# AUDIO.net
KiCad netlist of a schematic drawn in Altium Designer
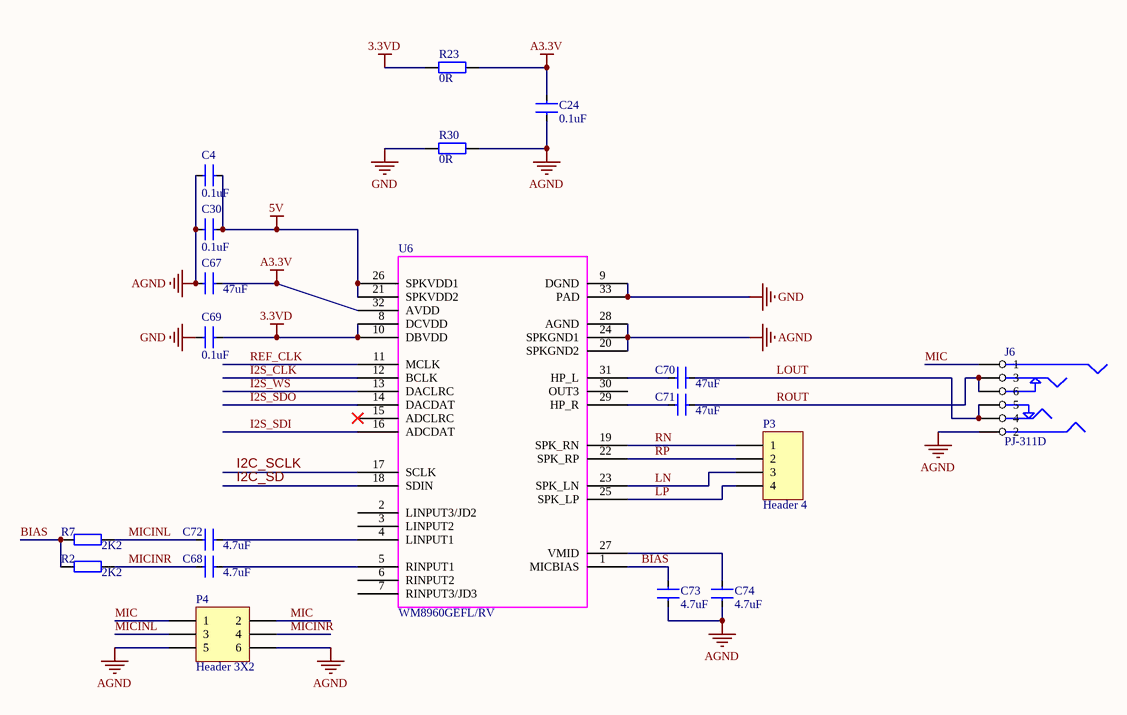
[diagram p0: AUDIO.SchDoc]

(export (version "E")
  (design (tool "Eeschema 10.0.6"))
  (components
    (comp (ref "C4")
      (value "0.1uF")
      (footprint "C0402")
      (description "普通小电容")
      (libsource (lib "LIB_MANGO") (part "CAP"))
    )
    (comp (ref "C24")
      (value "0.1uF")
      (footprint "C0402")
      (description "普通小电容")
      (libsource (lib "LIB_MANGO") (part "CAP"))
    )
    (comp (ref "C30")
      (value "0.1uF")
      (footprint "C0402")
      (description "普通小电容")
      (libsource (lib "LIB_MANGO") (part "CAP"))
    )
    (comp (ref "C67")
      (value "47uF")
      (footprint "0805C")
      (description "普通小电容")
      (libsource (lib "LIB_MANGO") (part "CAP"))
    )
    (comp (ref "C68")
      (value "4.7uF")
      (footprint "C0402")
      (description "普通小电容")
      (libsource (lib "LIB_MANGO") (part "CAP"))
    )
    (comp (ref "C69")
      (value "0.1uF")
      (footprint "C0402")
      (description "普通小电容")
      (libsource (lib "LIB_MANGO") (part "CAP"))
    )
    (comp (ref "C70")
      (value "47uF")
      (footprint "0805C")
      (description "普通小电容")
      (libsource (lib "LIB_MANGO") (part "CAP"))
    )
    (comp (ref "C71")
      (value "47uF")
      (footprint "0805C")
      (description "普通小电容")
      (libsource (lib "LIB_MANGO") (part "CAP"))
    )
    (comp (ref "C72")
      (value "4.7uF")
      (footprint "C0402")
      (description "普通小电容")
      (libsource (lib "LIB_MANGO") (part "CAP"))
    )
    (comp (ref "C73")
      (value "4.7uF")
      (footprint "C0402")
      (description "普通小电容")
      (libsource (lib "LIB_MANGO") (part "CAP"))
    )
    (comp (ref "C74")
      (value "4.7uF")
      (footprint "C0402")
      (description "普通小电容")
      (libsource (lib "LIB_MANGO") (part "CAP"))
    )
    (comp (ref "J6") (value "PJ-311D") (footprint "PJ311D") (libsource (lib "LIB_MANGO") (part "PJ-311D")))
    (comp (ref "P3")
      (value "Header 4")
      (footprint "HDR1X4 -2.0")
      (description "Header, 4-Pin")
      (fields (field (name "PUBLISHER") "Altium Limited"))
      (libsource (lib "LIB_MANGO") (part "Header 4"))
    )
    (comp (ref "P4")
      (value "Header 3X2")
      (footprint "HDR2X3 - 2.0")
      (description "Header, 3-Pin, Dual row")
      (fields (field (name "PUBLISHER") "Altium Limited"))
      (libsource (lib "LIB_MANGO") (part "Header 3X2"))
    )
    (comp (ref "R2")
      (value "2K2")
      (footprint "R0402")
      (description "普通电阻")
      (libsource (lib "LIB_MANGO") (part "RES"))
    )
    (comp (ref "R7")
      (value "2K2")
      (footprint "R0402")
      (description "普通电阻")
      (libsource (lib "LIB_MANGO") (part "RES"))
    )
    (comp (ref "R23")
      (value "0R")
      (footprint "R0402")
      (description "普通电阻")
      (libsource (lib "LIB_MANGO") (part "RES"))
    )
    (comp (ref "R30")
      (value "0R")
      (footprint "R0402")
      (description "普通电阻")
      (libsource (lib "LIB_MANGO") (part "RES"))
    )
    (comp (ref "U6")
      (value "WM8960GEFL/RV")
      (footprint "QFN50P500X500X100-33N")
      (libsource (lib "ALL") (part "WM8960GEFL/RV"))
    )
  )
  (nets
    (net (code "1") (name "/BIAS") (class "Default")
      (node (ref "C73") (pin "2") (pinfunction "2_2") (pintype "passive"))
      (node (ref "R2") (pin "1") (pinfunction "1_1") (pintype "passive"))
      (node (ref "R7") (pin "1") (pinfunction "1_1") (pintype "passive"))
      (node (ref "U6") (pin "1") (pinfunction "MICBIAS_1") (pintype "passive"))
    )
    (net (code "2") (name "/I2C_SCLK") (class "Default")
      (node (ref "U6") (pin "17") (pinfunction "SCLK_17") (pintype "passive"))
    )
    (net (code "3") (name "/I2C_SD") (class "Default")
      (node (ref "U6") (pin "18") (pinfunction "SDIN_18") (pintype "passive"))
    )
    (net (code "4") (name "/I2S_CLK") (class "Default")
      (node (ref "U6") (pin "12") (pinfunction "BCLK_12") (pintype "passive"))
    )
    (net (code "5") (name "/I2S_SDI") (class "Default")
      (node (ref "U6") (pin "16") (pinfunction "ADCDAT_16") (pintype "passive"))
    )
    (net (code "6") (name "/I2S_SDO") (class "Default")
      (node (ref "U6") (pin "14") (pinfunction "DACDAT_14") (pintype "passive"))
    )
    (net (code "7") (name "/I2S_WS") (class "Default")
      (node (ref "U6") (pin "13") (pinfunction "DACLRC_13") (pintype "passive"))
    )
    (net (code "8") (name "/LN") (class "Default")
      (node (ref "P3") (pin "3") (pinfunction "3_3") (pintype "passive"))
      (node (ref "U6") (pin "23") (pinfunction "SPK_LN_23") (pintype "passive"))
    )
    (net (code "9") (name "/LOUT") (class "Default")
      (node (ref "C70") (pin "1") (pinfunction "1_1") (pintype "passive"))
      (node (ref "J6") (pin "4") (pinfunction "4_4") (pintype "passive"))
      (node (ref "J6") (pin "5") (pinfunction "5_5") (pintype "passive"))
    )
    (net (code "10") (name "/LP") (class "Default")
      (node (ref "P3") (pin "4") (pinfunction "4_4") (pintype "passive"))
      (node (ref "U6") (pin "25") (pinfunction "SPK_LP_25") (pintype "passive"))
    )
    (net (code "11") (name "/MIC") (class "Default")
      (node (ref "J6") (pin "1") (pinfunction "1_1") (pintype "passive"))
      (node (ref "P4") (pin "1") (pinfunction "1_1") (pintype "passive"))
      (node (ref "P4") (pin "2") (pinfunction "2_2") (pintype "passive"))
    )
    (net (code "12") (name "/MICINL") (class "Default")
      (node (ref "C72") (pin "2") (pinfunction "2_2") (pintype "passive"))
      (node (ref "P4") (pin "3") (pinfunction "3_3") (pintype "passive"))
      (node (ref "R7") (pin "2") (pinfunction "2_2") (pintype "passive"))
    )
    (net (code "13") (name "/MICINR") (class "Default")
      (node (ref "C68") (pin "2") (pinfunction "2_2") (pintype "passive"))
      (node (ref "P4") (pin "4") (pinfunction "4_4") (pintype "passive"))
      (node (ref "R2") (pin "2") (pinfunction "2_2") (pintype "passive"))
    )
    (net (code "14") (name "/REF_CLK") (class "Default")
      (node (ref "U6") (pin "11") (pinfunction "MCLK_11") (pintype "passive"))
    )
    (net (code "15") (name "/RN") (class "Default")
      (node (ref "P3") (pin "1") (pinfunction "1_1") (pintype "passive"))
      (node (ref "U6") (pin "19") (pinfunction "SPK_RN_19") (pintype "passive"))
    )
    (net (code "16") (name "/ROUT") (class "Default")
      (node (ref "C71") (pin "1") (pinfunction "1_1") (pintype "passive"))
      (node (ref "J6") (pin "3") (pinfunction "3_3") (pintype "passive"))
      (node (ref "J6") (pin "6") (pinfunction "6_6") (pintype "passive"))
    )
    (net (code "17") (name "/RP") (class "Default")
      (node (ref "P3") (pin "2") (pinfunction "2_2") (pintype "passive"))
      (node (ref "U6") (pin "22") (pinfunction "SPK_RP_22") (pintype "passive"))
    )
    (net (code "18") (name "3.3VD") (class "Default")
      (node (ref "C69") (pin "2") (pinfunction "2_2") (pintype "passive"))
      (node (ref "R23") (pin "1") (pinfunction "1_1") (pintype "passive"))
      (node (ref "U6") (pin "10") (pinfunction "DBVDD_10") (pintype "passive"))
      (node (ref "U6") (pin "8") (pinfunction "DCVDD_8") (pintype "passive"))
    )
    (net (code "19") (name "5V") (class "Default")
      (node (ref "C30") (pin "1") (pinfunction "1_1") (pintype "passive"))
      (node (ref "C4") (pin "1") (pinfunction "1_1") (pintype "passive"))
      (node (ref "U6") (pin "21") (pinfunction "SPKVDD2_21") (pintype "passive"))
      (node (ref "U6") (pin "26") (pinfunction "SPKVDD1_26") (pintype "passive"))
    )
    (net (code "20") (name "A3.3V") (class "Default")
      (node (ref "C24") (pin "2") (pinfunction "2_2") (pintype "passive"))
      (node (ref "C67") (pin "2") (pinfunction "2_2") (pintype "passive"))
      (node (ref "R23") (pin "2") (pinfunction "2_2") (pintype "passive"))
      (node (ref "U6") (pin "32") (pinfunction "AVDD_32") (pintype "passive"))
    )
    (net (code "21") (name "AGND") (class "Default")
      (node (ref "C24") (pin "1") (pinfunction "1_1") (pintype "passive"))
      (node (ref "C30") (pin "2") (pinfunction "2_2") (pintype "passive"))
      (node (ref "C4") (pin "2") (pinfunction "2_2") (pintype "passive"))
      (node (ref "C67") (pin "1") (pinfunction "1_1") (pintype "passive"))
      (node (ref "C73") (pin "1") (pinfunction "1_1") (pintype "passive"))
      (node (ref "C74") (pin "1") (pinfunction "1_1") (pintype "passive"))
      (node (ref "J6") (pin "2") (pinfunction "2_2") (pintype "passive"))
      (node (ref "P4") (pin "5") (pinfunction "5_5") (pintype "passive"))
      (node (ref "P4") (pin "6") (pinfunction "6_6") (pintype "passive"))
      (node (ref "R30") (pin "2") (pinfunction "2_2") (pintype "passive"))
      (node (ref "U6") (pin "20") (pinfunction "SPKGND2_20") (pintype "passive"))
      (node (ref "U6") (pin "24") (pinfunction "SPKGND1_24") (pintype "passive"))
      (node (ref "U6") (pin "28") (pinfunction "AGND_28") (pintype "passive"))
    )
    (net (code "22") (name "GND") (class "Default")
      (node (ref "C69") (pin "1") (pinfunction "1_1") (pintype "passive"))
      (node (ref "R30") (pin "1") (pinfunction "1_1") (pintype "passive"))
      (node (ref "U6") (pin "33") (pinfunction "PAD_33") (pintype "passive"))
      (node (ref "U6") (pin "9") (pinfunction "DGND_9") (pintype "passive"))
    )
    (net (code "23") (name "Net-(U6-HP_L)") (class "Default")
      (node (ref "C70") (pin "2") (pinfunction "2_2") (pintype "passive"))
      (node (ref "U6") (pin "31") (pinfunction "HP_L_31") (pintype "passive"))
    )
    (net (code "24") (name "Net-(U6-HP_R)") (class "Default")
      (node (ref "C71") (pin "2") (pinfunction "2_2") (pintype "passive"))
      (node (ref "U6") (pin "29") (pinfunction "HP_R_29") (pintype "passive"))
    )
    (net (code "25") (name "Net-(U6-LINPUT1)") (class "Default")
      (node (ref "C72") (pin "1") (pinfunction "1_1") (pintype "passive"))
      (node (ref "U6") (pin "4") (pinfunction "LINPUT1_4") (pintype "passive"))
    )
    (net (code "26") (name "Net-(U6-RINPUT1)") (class "Default")
      (node (ref "C68") (pin "1") (pinfunction "1_1") (pintype "passive"))
      (node (ref "U6") (pin "5") (pinfunction "RINPUT1_5") (pintype "passive"))
    )
    (net (code "27") (name "Net-(U6-VMID)") (class "Default")
      (node (ref "C74") (pin "2") (pinfunction "2_2") (pintype "passive"))
      (node (ref "U6") (pin "27") (pinfunction "VMID_27") (pintype "passive"))
    )
    (net (code "28") (name "unconnected-(U6-ADCLRC-Pad15)") (class "Default")
      (node (ref "U6") (pin "15") (pinfunction "ADCLRC_15") (pintype "passive+no_connect"))
    )
    (net (code "29") (name "unconnected-(U6-LINPUT2-Pad3)") (class "Default")
      (node (ref "U6") (pin "3") (pinfunction "LINPUT2_3") (pintype "passive"))
    )
    (net (code "30") (name "unconnected-(U6-LINPUT3{slash}JD2-Pad2)") (class "Default")
      (node (ref "U6") (pin "2") (pinfunction "LINPUT3/JD2_2") (pintype "passive"))
    )
    (net (code "31") (name "unconnected-(U6-OUT3-Pad30)") (class "Default")
      (node (ref "U6") (pin "30") (pinfunction "OUT3_30") (pintype "passive"))
    )
    (net (code "32") (name "unconnected-(U6-RINPUT2-Pad6)") (class "Default")
      (node (ref "U6") (pin "6") (pinfunction "RINPUT2_6") (pintype "passive"))
    )
    (net (code "33") (name "unconnected-(U6-RINPUT3{slash}JD3-Pad7)") (class "Default")
      (node (ref "U6") (pin "7") (pinfunction "RINPUT3/JD3_7") (pintype "passive"))
    )
  )
)
